# LED_PCB.net
KiCad netlist of a schematic drawn in Altium Designer
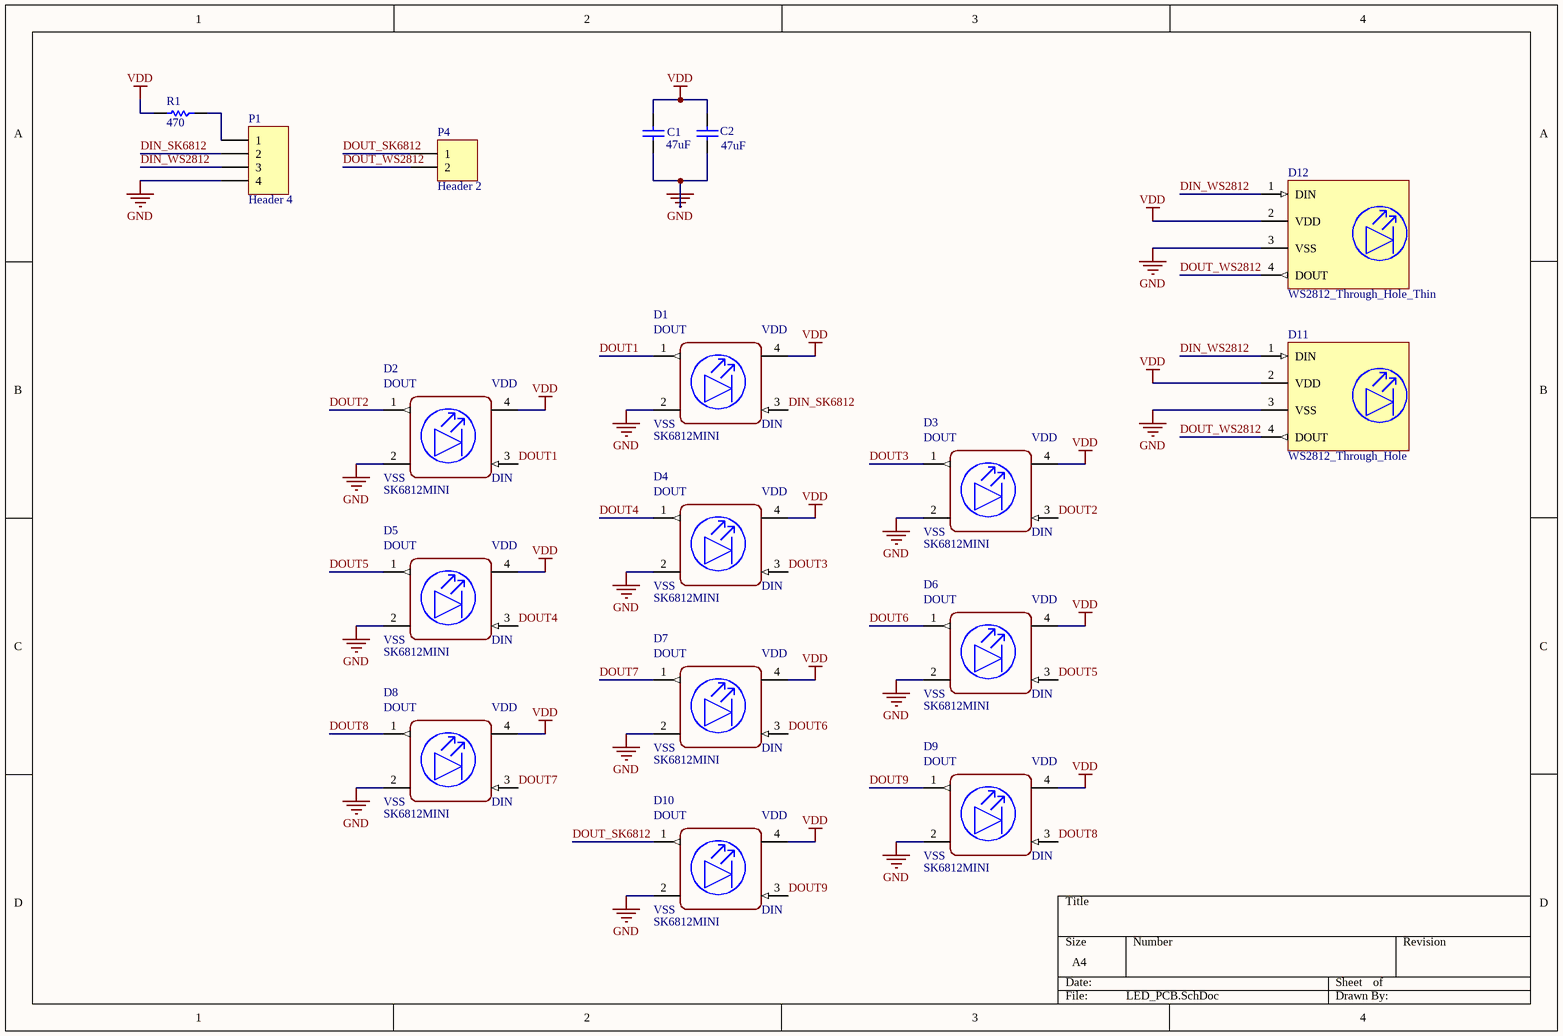
[diagram p0: LED_PCB.SchDoc]

(export (version "E")
  (design (tool "Eeschema 10.0.6"))
  (components
    (comp (ref "C1")
      (value "47uF")
      (footprint "0805C")
      (description "Capacitor")
      (fields (field (name "REVIEWED BY") "RM - 2018/08/05"))
      (libsource (lib "DSO") (part "C"))
    )
    (comp (ref "C2")
      (value "47uF")
      (footprint "0805C")
      (description "Capacitor")
      (fields (field (name "REVIEWED BY") "RM - 2018/08/05"))
      (libsource (lib "DSO") (part "C"))
    )
    (comp (ref "D1")
      (value "Diode_SK6812MINI")
      (footprint "SK6812MINI")
      (description "SMD LED 3535")
      (fields (field (name "MANUFACTURER") "Adafruit") (field (name "PART NUMBER") "SK6812MINI"))
      (libsource (lib "Diode_LED") (part "Diode_SK6812MINI"))
    )
    (comp (ref "D2")
      (value "Diode_SK6812MINI")
      (footprint "SK6812MINI")
      (description "SMD LED 3535")
      (fields (field (name "MANUFACTURER") "Adafruit") (field (name "PART NUMBER") "SK6812MINI"))
      (libsource (lib "Diode_LED") (part "Diode_SK6812MINI"))
    )
    (comp (ref "D3")
      (value "Diode_SK6812MINI")
      (footprint "SK6812MINI")
      (description "SMD LED 3535")
      (fields (field (name "MANUFACTURER") "Adafruit") (field (name "PART NUMBER") "SK6812MINI"))
      (libsource (lib "Diode_LED") (part "Diode_SK6812MINI"))
    )
    (comp (ref "D4")
      (value "Diode_SK6812MINI")
      (footprint "SK6812MINI")
      (description "SMD LED 3535")
      (fields (field (name "MANUFACTURER") "Adafruit") (field (name "PART NUMBER") "SK6812MINI"))
      (libsource (lib "Diode_LED") (part "Diode_SK6812MINI"))
    )
    (comp (ref "D5")
      (value "Diode_SK6812MINI")
      (footprint "SK6812MINI")
      (description "SMD LED 3535")
      (fields (field (name "MANUFACTURER") "Adafruit") (field (name "PART NUMBER") "SK6812MINI"))
      (libsource (lib "Diode_LED") (part "Diode_SK6812MINI"))
    )
    (comp (ref "D6")
      (value "Diode_SK6812MINI")
      (footprint "SK6812MINI")
      (description "SMD LED 3535")
      (fields (field (name "MANUFACTURER") "Adafruit") (field (name "PART NUMBER") "SK6812MINI"))
      (libsource (lib "Diode_LED") (part "Diode_SK6812MINI"))
    )
    (comp (ref "D7")
      (value "Diode_SK6812MINI")
      (footprint "SK6812MINI")
      (description "SMD LED 3535")
      (fields (field (name "MANUFACTURER") "Adafruit") (field (name "PART NUMBER") "SK6812MINI"))
      (libsource (lib "Diode_LED") (part "Diode_SK6812MINI"))
    )
    (comp (ref "D8")
      (value "Diode_SK6812MINI")
      (footprint "SK6812MINI")
      (description "SMD LED 3535")
      (fields (field (name "MANUFACTURER") "Adafruit") (field (name "PART NUMBER") "SK6812MINI"))
      (libsource (lib "Diode_LED") (part "Diode_SK6812MINI"))
    )
    (comp (ref "D9")
      (value "Diode_SK6812MINI")
      (footprint "SK6812MINI")
      (description "SMD LED 3535")
      (fields (field (name "MANUFACTURER") "Adafruit") (field (name "PART NUMBER") "SK6812MINI"))
      (libsource (lib "Diode_LED") (part "Diode_SK6812MINI"))
    )
    (comp (ref "D10")
      (value "Diode_SK6812MINI")
      (footprint "SK6812MINI")
      (description "SMD LED 3535")
      (fields (field (name "MANUFACTURER") "Adafruit") (field (name "PART NUMBER") "SK6812MINI"))
      (libsource (lib "Diode_LED") (part "Diode_SK6812MINI"))
    )
    (comp (ref "D11")
      (value "WS2812_Through_Hole")
      (footprint "WS2812_Through_Hole")
      (libsource (lib "Diode_LED") (part "WS2812_Through_Hole"))
    )
    (comp (ref "D12")
      (value "WS2812_Through_Hole_Thin")
      (footprint "WS2812_Through_Hole_smaller")
      (description "WS2812 Through Hole LED")
      (libsource (lib "Diode_LED") (part "WS2812_Through_Hole_Thin"))
    )
    (comp (ref "P1")
      (value "Header 4")
      (footprint "HDR1X4")
      (description "Header, 4-Pin")
      (fields (field (name "PUBLISHER") "Altium Limited"))
      (libsource (lib "Miscellaneous Connectors") (part "Header 4"))
    )
    (comp (ref "P4")
      (value "Header 2")
      (footprint "HDR1X2")
      (description "Header, 2-Pin")
      (fields (field (name "PUBLISHER") "Altium Limited"))
      (libsource (lib "Miscellaneous Connectors") (part "Header 2"))
    )
    (comp (ref "R1")
      (value "470")
      (footprint "0805")
      (description "Resistor")
      (fields (field (name "REVIEWED BY") "RM - 2018/08/05"))
      (libsource (lib "DSO") (part "R"))
    )
  )
  (nets
    (net (code "1") (name "/DIN_SK6812") (class "Default")
      (node (ref "D1") (pin "3") (pinfunction "DIN_3") (pintype "input"))
      (node (ref "P1") (pin "2") (pinfunction "2_2") (pintype "passive"))
    )
    (net (code "2") (name "/DIN_WS2812") (class "Default")
      (node (ref "D11") (pin "1") (pinfunction "DIN_1") (pintype "input"))
      (node (ref "D12") (pin "1") (pinfunction "DIN_1") (pintype "input"))
      (node (ref "P1") (pin "3") (pinfunction "3_3") (pintype "passive"))
    )
    (net (code "3") (name "/DOUT1") (class "Default")
      (node (ref "D1") (pin "1") (pinfunction "DOUT_1") (pintype "output"))
      (node (ref "D2") (pin "3") (pinfunction "DIN_3") (pintype "input"))
    )
    (net (code "4") (name "/DOUT2") (class "Default")
      (node (ref "D2") (pin "1") (pinfunction "DOUT_1") (pintype "output"))
      (node (ref "D3") (pin "3") (pinfunction "DIN_3") (pintype "input"))
    )
    (net (code "5") (name "/DOUT3") (class "Default")
      (node (ref "D3") (pin "1") (pinfunction "DOUT_1") (pintype "output"))
      (node (ref "D4") (pin "3") (pinfunction "DIN_3") (pintype "input"))
    )
    (net (code "6") (name "/DOUT4") (class "Default")
      (node (ref "D4") (pin "1") (pinfunction "DOUT_1") (pintype "output"))
      (node (ref "D5") (pin "3") (pinfunction "DIN_3") (pintype "input"))
    )
    (net (code "7") (name "/DOUT5") (class "Default")
      (node (ref "D5") (pin "1") (pinfunction "DOUT_1") (pintype "output"))
      (node (ref "D6") (pin "3") (pinfunction "DIN_3") (pintype "input"))
    )
    (net (code "8") (name "/DOUT6") (class "Default")
      (node (ref "D6") (pin "1") (pinfunction "DOUT_1") (pintype "output"))
      (node (ref "D7") (pin "3") (pinfunction "DIN_3") (pintype "input"))
    )
    (net (code "9") (name "/DOUT7") (class "Default")
      (node (ref "D7") (pin "1") (pinfunction "DOUT_1") (pintype "output"))
      (node (ref "D8") (pin "3") (pinfunction "DIN_3") (pintype "input"))
    )
    (net (code "10") (name "/DOUT8") (class "Default")
      (node (ref "D8") (pin "1") (pinfunction "DOUT_1") (pintype "output"))
      (node (ref "D9") (pin "3") (pinfunction "DIN_3") (pintype "input"))
    )
    (net (code "11") (name "/DOUT9") (class "Default")
      (node (ref "D10") (pin "3") (pinfunction "DIN_3") (pintype "input"))
      (node (ref "D9") (pin "1") (pinfunction "DOUT_1") (pintype "output"))
    )
    (net (code "12") (name "/DOUT_SK6812") (class "Default")
      (node (ref "D10") (pin "1") (pinfunction "DOUT_1") (pintype "output"))
      (node (ref "P4") (pin "1") (pinfunction "1_1") (pintype "passive"))
    )
    (net (code "13") (name "/DOUT_WS2812") (class "Default")
      (node (ref "D11") (pin "4") (pinfunction "DOUT_4") (pintype "output"))
      (node (ref "D12") (pin "4") (pinfunction "DOUT_4") (pintype "output"))
      (node (ref "P4") (pin "2") (pinfunction "2_2") (pintype "passive"))
    )
    (net (code "14") (name "GND") (class "Default")
      (node (ref "C1") (pin "2") (pinfunction "2_2") (pintype "passive"))
      (node (ref "C2") (pin "2") (pinfunction "2_2") (pintype "passive"))
      (node (ref "D1") (pin "2") (pinfunction "VSS_2") (pintype "power_in"))
      (node (ref "D10") (pin "2") (pinfunction "VSS_2") (pintype "power_in"))
      (node (ref "D11") (pin "3") (pinfunction "VSS_3") (pintype "power_in"))
      (node (ref "D12") (pin "3") (pinfunction "VSS_3") (pintype "power_in"))
      (node (ref "D2") (pin "2") (pinfunction "VSS_2") (pintype "power_in"))
      (node (ref "D3") (pin "2") (pinfunction "VSS_2") (pintype "power_in"))
      (node (ref "D4") (pin "2") (pinfunction "VSS_2") (pintype "power_in"))
      (node (ref "D5") (pin "2") (pinfunction "VSS_2") (pintype "power_in"))
      (node (ref "D6") (pin "2") (pinfunction "VSS_2") (pintype "power_in"))
      (node (ref "D7") (pin "2") (pinfunction "VSS_2") (pintype "power_in"))
      (node (ref "D8") (pin "2") (pinfunction "VSS_2") (pintype "power_in"))
      (node (ref "D9") (pin "2") (pinfunction "VSS_2") (pintype "power_in"))
      (node (ref "P1") (pin "4") (pinfunction "4_4") (pintype "passive"))
    )
    (net (code "15") (name "Net-(P1-Pad1)") (class "Default")
      (node (ref "P1") (pin "1") (pinfunction "1_1") (pintype "passive"))
      (node (ref "R1") (pin "1") (pintype "passive"))
    )
    (net (code "16") (name "VDD") (class "Default")
      (node (ref "C1") (pin "1") (pinfunction "1_1") (pintype "passive"))
      (node (ref "C2") (pin "1") (pinfunction "1_1") (pintype "passive"))
      (node (ref "D1") (pin "4") (pinfunction "VDD_4") (pintype "power_in"))
      (node (ref "D10") (pin "4") (pinfunction "VDD_4") (pintype "power_in"))
      (node (ref "D11") (pin "2") (pinfunction "VDD_2") (pintype "power_in"))
      (node (ref "D12") (pin "2") (pinfunction "VDD_2") (pintype "power_in"))
      (node (ref "D2") (pin "4") (pinfunction "VDD_4") (pintype "power_in"))
      (node (ref "D3") (pin "4") (pinfunction "VDD_4") (pintype "power_in"))
      (node (ref "D4") (pin "4") (pinfunction "VDD_4") (pintype "power_in"))
      (node (ref "D5") (pin "4") (pinfunction "VDD_4") (pintype "power_in"))
      (node (ref "D6") (pin "4") (pinfunction "VDD_4") (pintype "power_in"))
      (node (ref "D7") (pin "4") (pinfunction "VDD_4") (pintype "power_in"))
      (node (ref "D8") (pin "4") (pinfunction "VDD_4") (pintype "power_in"))
      (node (ref "D9") (pin "4") (pinfunction "VDD_4") (pintype "power_in"))
      (node (ref "R1") (pin "2") (pintype "passive"))
    )
  )
)
